# SpectroSlave.net
KiCad netlist of a schematic drawn in EAGLE
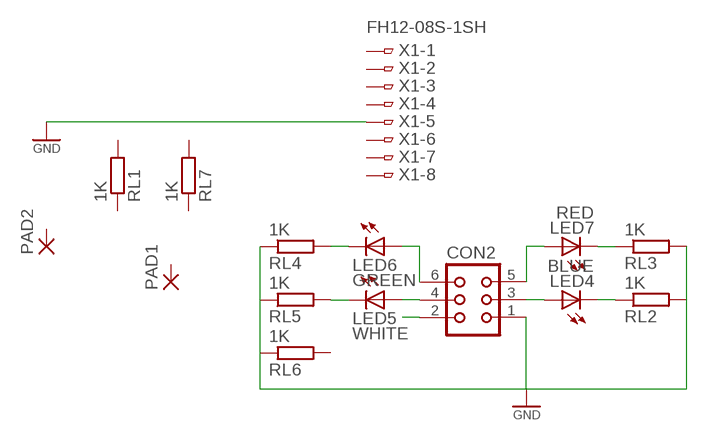
[diagram p0: schematic, sheet 1]

(export (version "E")
  (design (tool "Eeschema 10.0.6"))
  (components
    (comp (ref "CON2")
      (value "CON06L")
      (footprint "eagle-import:CON06L")
      (libsource (lib "eagle-import") (part "CON06L"))
    )
    (comp (ref "LED4")
      (value "BLUE")
      (footprint "eagle-import:CHIP-LED0805")
      (libsource (lib "eagle-import") (part "LEDCHIP-LED0805"))
    )
    (comp (ref "LED5")
      (value "WHITE")
      (footprint "eagle-import:CHIP-LED0805")
      (libsource (lib "eagle-import") (part "LEDCHIP-LED0805"))
    )
    (comp (ref "LED6")
      (value "GREEN")
      (footprint "eagle-import:CHIP-LED0805")
      (libsource (lib "eagle-import") (part "LEDCHIP-LED0805"))
    )
    (comp (ref "LED7")
      (value "RED")
      (footprint "eagle-import:CHIP-LED0805")
      (libsource (lib "eagle-import") (part "LEDCHIP-LED0805"))
    )
    (comp (ref "PAD1")
      (value "SMD5")
      (footprint "eagle-import:SMD2,54-5,08")
      (libsource (lib "eagle-import") (part "SMD5"))
    )
    (comp (ref "PAD2")
      (value "SMD5")
      (footprint "eagle-import:SMD2,54-5,08")
      (libsource (lib "eagle-import") (part "SMD5"))
    )
    (comp (ref "RL1")
      (value "1K")
      (footprint "eagle-import:R0805")
      (libsource (lib "eagle-import") (part "R-EU_R0805"))
    )
    (comp (ref "RL2")
      (value "1K")
      (footprint "eagle-import:R0805")
      (libsource (lib "eagle-import") (part "R-EU_R0805"))
    )
    (comp (ref "RL3")
      (value "1K")
      (footprint "eagle-import:R0805")
      (libsource (lib "eagle-import") (part "R-EU_R0805"))
    )
    (comp (ref "RL4")
      (value "1K")
      (footprint "eagle-import:R0805")
      (libsource (lib "eagle-import") (part "R-EU_R0805"))
    )
    (comp (ref "RL5")
      (value "1K")
      (footprint "eagle-import:R0805")
      (libsource (lib "eagle-import") (part "R-EU_R0805"))
    )
    (comp (ref "RL6")
      (value "1K")
      (footprint "eagle-import:R0805")
      (libsource (lib "eagle-import") (part "R-EU_R0805"))
    )
    (comp (ref "RL7")
      (value "1K")
      (footprint "eagle-import:R0805")
      (libsource (lib "eagle-import") (part "R-EU_R0805"))
    )
    (comp (ref "X1")
      (value "FH12-08S-1SH")
      (footprint "eagle-import:FH12-08S-1SH")
      (libsource (lib "eagle-import") (part "FH12-08S-1SH"))
    )
  )
  (nets
    (net (code "1") (name "GND") (class "Default")
      (node (ref "CON2") (pin "1") (pinfunction "1_1") (pintype "passive"))
      (node (ref "RL2") (pin "2") (pinfunction "2_2") (pintype "passive"))
      (node (ref "RL3") (pin "2") (pinfunction "2_2") (pintype "passive"))
      (node (ref "RL4") (pin "1") (pinfunction "1_1") (pintype "passive"))
      (node (ref "RL5") (pin "1") (pinfunction "1_1") (pintype "passive"))
      (node (ref "RL6") (pin "1") (pinfunction "1_1") (pintype "passive"))
      (node (ref "X1") (pin "5") (pinfunction "1_5") (pintype "passive"))
    )
    (net (code "2") (name "Net-(CON2-Pad3)") (class "Default")
      (node (ref "CON2") (pin "3") (pinfunction "3_3") (pintype "passive"))
      (node (ref "LED4") (pin "A") (pinfunction "A_A") (pintype "passive"))
    )
    (net (code "3") (name "Net-(CON2-Pad4)") (class "Default")
      (node (ref "CON2") (pin "4") (pinfunction "4_4") (pintype "passive"))
      (node (ref "LED5") (pin "A") (pinfunction "A_A") (pintype "passive"))
    )
    (net (code "4") (name "Net-(CON2-Pad5)") (class "Default")
      (node (ref "CON2") (pin "5") (pinfunction "5_5") (pintype "passive"))
      (node (ref "LED7") (pin "A") (pinfunction "A_A") (pintype "passive"))
    )
    (net (code "5") (name "Net-(CON2-Pad6)") (class "Default")
      (node (ref "CON2") (pin "6") (pinfunction "6_6") (pintype "passive"))
      (node (ref "LED6") (pin "A") (pinfunction "A_A") (pintype "passive"))
    )
    (net (code "6") (name "Net-(LED4-PadC)") (class "Default")
      (node (ref "LED4") (pin "C") (pinfunction "C_C") (pintype "passive"))
      (node (ref "RL2") (pin "1") (pinfunction "1_1") (pintype "passive"))
    )
    (net (code "7") (name "Net-(LED5-PadC)") (class "Default")
      (node (ref "LED5") (pin "C") (pinfunction "C_C") (pintype "passive"))
      (node (ref "RL5") (pin "2") (pinfunction "2_2") (pintype "passive"))
    )
    (net (code "8") (name "Net-(LED6-PadC)") (class "Default")
      (node (ref "LED6") (pin "C") (pinfunction "C_C") (pintype "passive"))
      (node (ref "RL4") (pin "2") (pinfunction "2_2") (pintype "passive"))
    )
    (net (code "9") (name "Net-(LED7-PadC)") (class "Default")
      (node (ref "LED7") (pin "C") (pinfunction "C_C") (pintype "passive"))
      (node (ref "RL3") (pin "1") (pinfunction "1_1") (pintype "passive"))
    )
    (net (code "10") (name "unconnected-(CON2-Pad2)") (class "Default")
      (node (ref "CON2") (pin "2") (pinfunction "2_2") (pintype "passive"))
    )
    (net (code "11") (name "unconnected-(PAD1-P-Pad1)") (class "Default")
      (node (ref "PAD1") (pin "1") (pinfunction "P_1") (pintype "passive"))
    )
    (net (code "12") (name "unconnected-(PAD2-P-Pad1)") (class "Default")
      (node (ref "PAD2") (pin "1") (pinfunction "P_1") (pintype "passive"))
    )
    (net (code "13") (name "unconnected-(RL1-Pad1)") (class "Default")
      (node (ref "RL1") (pin "1") (pinfunction "1_1") (pintype "passive"))
    )
    (net (code "14") (name "unconnected-(RL1-Pad2)") (class "Default")
      (node (ref "RL1") (pin "2") (pinfunction "2_2") (pintype "passive"))
    )
    (net (code "15") (name "unconnected-(RL6-Pad2)") (class "Default")
      (node (ref "RL6") (pin "2") (pinfunction "2_2") (pintype "passive"))
    )
    (net (code "16") (name "unconnected-(RL7-Pad1)") (class "Default")
      (node (ref "RL7") (pin "1") (pinfunction "1_1") (pintype "passive"))
    )
    (net (code "17") (name "unconnected-(RL7-Pad2)") (class "Default")
      (node (ref "RL7") (pin "2") (pinfunction "2_2") (pintype "passive"))
    )
    (net (code "18") (name "unconnected-(X1-Pad1)") (class "Default")
      (node (ref "X1") (pin "1") (pinfunction "1_1") (pintype "passive"))
    )
    (net (code "19") (name "unconnected-(X1B-1-Pad2)") (class "Default")
      (node (ref "X1") (pin "2") (pinfunction "1_2") (pintype "passive"))
    )
    (net (code "20") (name "unconnected-(X1C-1-Pad3)") (class "Default")
      (node (ref "X1") (pin "3") (pinfunction "1_3") (pintype "passive"))
    )
    (net (code "21") (name "unconnected-(X1D-1-Pad4)") (class "Default")
      (node (ref "X1") (pin "4") (pinfunction "1_4") (pintype "passive"))
    )
    (net (code "22") (name "unconnected-(X1F-1-Pad6)") (class "Default")
      (node (ref "X1") (pin "6") (pinfunction "1_6") (pintype "passive"))
    )
    (net (code "23") (name "unconnected-(X1G-1-Pad7)") (class "Default")
      (node (ref "X1") (pin "7") (pinfunction "1_7") (pintype "passive"))
    )
    (net (code "24") (name "unconnected-(X1H-1-Pad8)") (class "Default")
      (node (ref "X1") (pin "8") (pinfunction "1_8") (pintype "passive"))
    )
  )
)
